# Controller_Board_Interface.net
KiCad netlist of a schematic drawn in Altium Designer
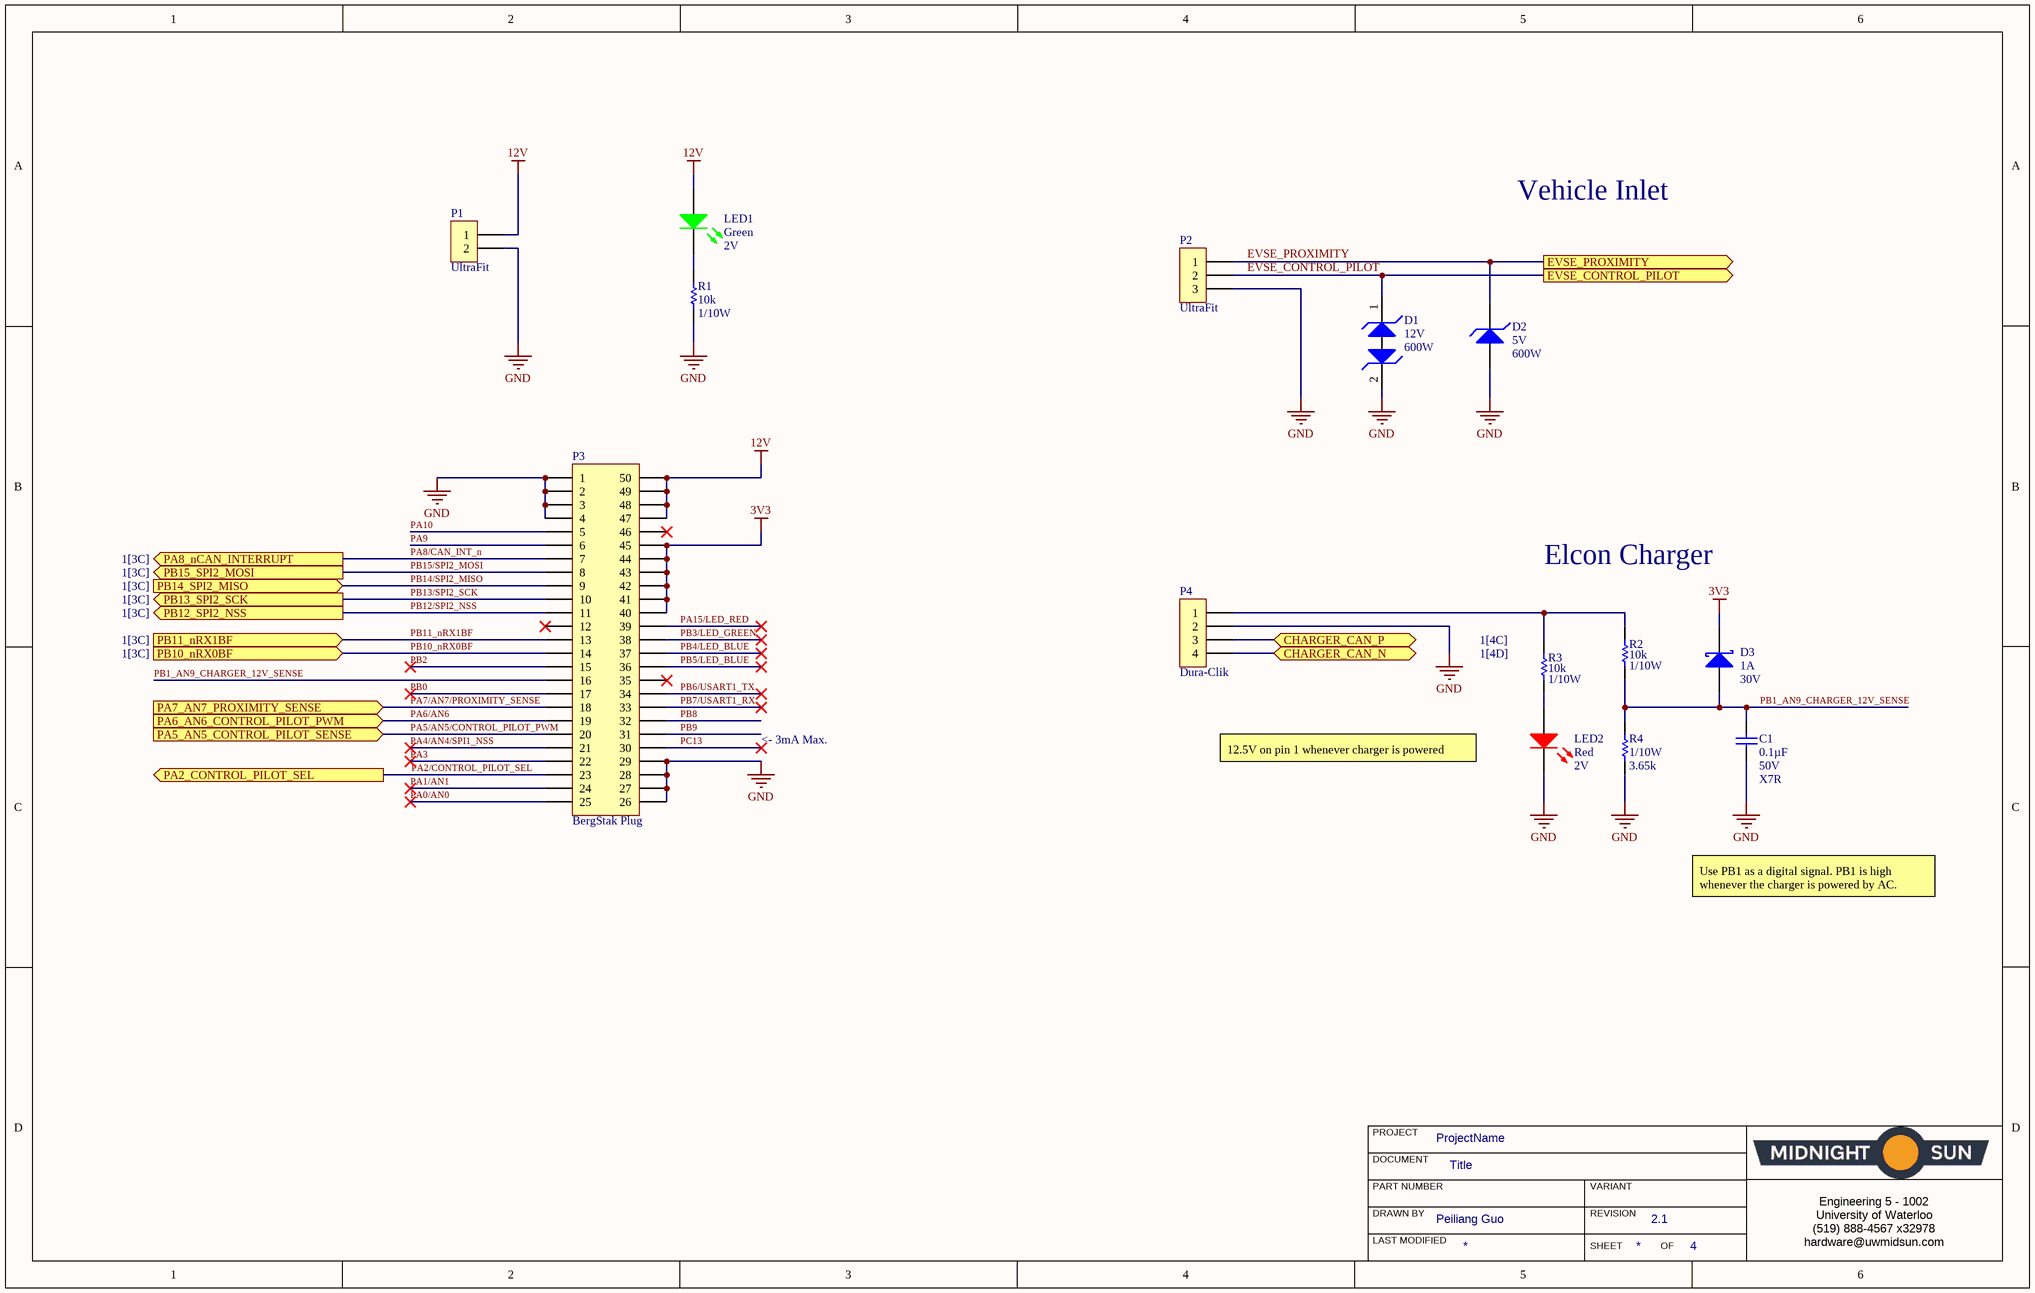
[diagram p0: Controller_Board_Interface.SchDoc]

(export (version "E")
  (design (tool "Eeschema 10.0.6"))
  (components
    (comp (ref "C1")
      (value "CAP CER 0.1UF 50V 10% X7R 0603")
      (footprint "CAP, 0603")
      (description "0.10µF ±10% 50V Ceramic Capacitor X7R 0603 (1608 Metric)")
      (fields
        (field (name "TOLERANCE") "±10%")
        (field (name "CAPACITANCE") "0.1µF")
        (field (name "VOLTAGE") "50V")
        (field (name "TEMPERATURE COEFFICIENT") "X7R")
      )
      (libsource (lib "altium-import") (part "root_0_CAP CER 0.1UF 50V 10% X7R 0603_"))
    )
    (comp (ref "D1")
      (value "DIODE TVS 12VWM 19.6VC DO-214AA (SMB)")
      (footprint "DO-214AA Diode")
      (description "TVS DIODE 12V 19.6V DO214AA")
      (fields
        (field (name "MANUFACTURER") "Vishay Semiconductor Diodes Division")
        (field (name "MANUFACTURER PART NUMBER") "SMBJ12CD-M3/H")
        (field (name "VOLTAGE - REVERSE STANDOFF (TYP)") "12V")
        (field (name "POWER - PEAK PULSE") "600W")
      )
      (libsource (lib "Schematic Diagrams") (part "DIODE TVS 12VWM 19.6VC DO-214AA (SMB)"))
    )
    (comp (ref "D2")
      (value "DIODE TVS 5VWM 9.1VC DO-214AA (SMB)")
      (footprint "DO-214AA Diode")
      (description "TVS DIODE 5V 9.1V DO214AA")
      (fields
        (field (name "MANUFACTURER") "Vishay Semiconductor Diodes Division")
        (field (name "MANUFACTURER PART NUMBER") "SMBJ5.0D-M3/H")
        (field (name "VOLTAGE - REVERSE STANDOFF (TYP)") "5V")
        (field (name "POWER - PEAK PULSE") "600W")
      )
      (libsource (lib "Schematic Diagrams") (part "DIODE TVS 5VWM 9.1VC DO-214AA (SMB)"))
    )
    (comp (ref "D3")
      (value "DIODE SCHOTTKY 30V 1A POWERDI123")
      (footprint "DIODE SCHOTTKY 30V 1A POWERDI123")
      (description "Diode Schottky 30V 1A Surface Mount PowerDI™ 123")
      (fields
        (field (name "MANUFACTURER") "Diodes Incorporated")
        (field (name "MANUFACTURER PART NUMBER") "DFLS130L-7")
        (field (name "CURRENT - AVERAGE RECTIFIED (IO)") "1A")
        (field (name "VOLTAGE - DC REVERSE (VR) (MAX)") "30V")
      )
      (libsource (lib "Schematic Diagrams") (part "DIODE SCHOTTKY 30V 1A POWERDI123"))
    )
    (comp (ref "LED1")
      (value "LED GREEN CLEAR 2V 0603")
      (footprint "LED_0603")
      (description "Green 572nm LED Indication - Discrete 2V 0603 (1608 Metric)")
      (fields
        (field (name "MANUFACTURER") "Wurth Electronics Inc.")
        (field (name "MANUFACTURER PART NUMBER") "150060VS75000")
        (field (name "COLOR") "Green")
        (field (name "VOLTAGE - FORWARD (VF) (TYP)") "2V")
      )
      (libsource (lib "Schematic Diagrams") (part "LED GREEN CLEAR 2V 0603"))
    )
    (comp (ref "LED2")
      (value "LED RED CLEAR 2V 0603")
      (footprint "LED_0603")
      (description "Red 631nm LED Indication - Discrete 2V 0603 (1608 Metric)")
      (fields
        (field (name "MANUFACTURER") "Wurth Electronics Inc.")
        (field (name "MANUFACTURER PART NUMBER") "150060RS75000")
        (field (name "COLOR") "Red")
        (field (name "VOLTAGE - FORWARD (VF) (TYP)") "2V")
      )
      (libsource (lib "altium-import") (part "root_3_LED RED CLEAR 2V 0603_"))
    )
    (comp (ref "P1")
      (value "CONN 2POS ULTRA-FIT 0.138\"")
      (footprint "CONN, 2POS ULTRA-FIT")
      (description "2 Positions Header, Shrouded Connector 0.138\" (3.50mm) Through Hole Gold")
      (fields (field (name "VOLTAGE") "400V") (field (name "SERIES") "UltraFit"))
      (libsource (lib "Schematic Diagrams") (part "CONN 2POS ULTRA-FIT 0.138{dblquote}"))
    )
    (comp (ref "P2")
      (value "CONN 3POS ULTRA-FIT 0.138\"")
      (footprint "CONN, 3POS ULTRA-FIT")
      (description "3 Positions Header Connector 0.138\" (3.50mm) Through Hole Tin")
      (fields (field (name "VOLTAGE") "400V") (field (name "SERIES") "UltraFit"))
      (libsource (lib "altium-import") (part "root_0_CONN 3POS ULTRA-FIT 0.138{dblquote}_"))
    )
    (comp (ref "P3")
      (value "CONN 50POS Bergstak Plug 0.02\"")
      (footprint "CONN, Bergstak 50 Pos Plug")
      (description "50 Position Connector Plug, Outer Shroud Contacts Surface Mount Gold")
      (fields (field (name "SERIES") "BergStak Plug"))
      (libsource (lib "Schematic Diagrams") (part "CONN 50POS Bergstak Plug 0.02{dblquote}"))
    )
    (comp (ref "P4")
      (value "Dura-Clik")
      (footprint "CONN, 4POS DURA-CLIK VERT")
      (description "4 Positions Header Connector 0.079\" (2.00mm) Surface Mount Tin")
      (fields
        (field (name "MANUFACTURER") "Molex, LLC")
        (field (name "MANUFACTURER PART NUMBER") "5600200420")
      )
      (libsource (lib "Schematic Diagrams") (part "CONN 4POS DURA-CLIK 0.079{dblquote}"))
    )
    (comp (ref "R1")
      (value "RES 10K OHM 1% 1/10W 0603")
      (footprint "RES, 0603")
      (description "RES SMD 10K OHM 1% 1/10W 0603")
      (fields
        (field (name "TOLERANCE") "±1%")
        (field (name "RESISTANCE") "10k")
        (field (name "POWER") "1/10W")
      )
      (libsource (lib "Schematic Diagrams") (part "RES 10K OHM 1% 1/10W 0603"))
    )
    (comp (ref "R2")
      (value "RES 10K OHM 1% 1/10W 0603")
      (footprint "RES, 0603")
      (description "RES SMD 10K OHM 1% 1/10W 0603")
      (fields
        (field (name "TOLERANCE") "±1%")
        (field (name "RESISTANCE") "10k")
        (field (name "POWER") "1/10W")
      )
      (libsource (lib "Schematic Diagrams") (part "RES 10K OHM 1% 1/10W 0603"))
    )
    (comp (ref "R3")
      (value "RES 10K OHM 1% 1/10W 0603")
      (footprint "RES, 0603")
      (description "RES SMD 10K OHM 1% 1/10W 0603")
      (fields
        (field (name "TOLERANCE") "±1%")
        (field (name "RESISTANCE") "10k")
        (field (name "POWER") "1/10W")
      )
      (libsource (lib "Schematic Diagrams") (part "RES 10K OHM 1% 1/10W 0603"))
    )
    (comp (ref "R4")
      (value "RES 3.65K OHM 0.1% 1/10W 0603")
      (footprint "RES, 0603")
      (description "3.65 kOhms ±0.1% 0.1W, 1/10W Chip Resistor 0603 (1608 Metric) Automotive AEC-Q200 Thin Film")
      (fields
        (field (name "MANUFACTURER") "Panasonic")
        (field (name "MANUFACTURER PART NUMBER") "ERA3AEB3651V")
        (field (name "POWER RATING") "1/10W")
        (field (name "RESISTANCE") "3.65k")
      )
      (libsource (lib "Schematic Diagrams") (part "RES 3.65K OHM 0.1% 1/10W 0603"))
    )
  )
  (nets
    (net (code "1") (name "/CHARGER_CAN_N") (class "Default")
      (node (ref "P4") (pin "4") (pinfunction "4_4") (pintype "passive"))
    )
    (net (code "2") (name "/CHARGER_CAN_P") (class "Default")
      (node (ref "P4") (pin "3") (pinfunction "3_3") (pintype "passive"))
    )
    (net (code "3") (name "/EVSE_CONTROL_PILOT") (class "Default")
      (node (ref "D1") (pin "1") (pinfunction "Cathode1_1") (pintype "passive"))
      (node (ref "P2") (pin "2") (pinfunction "2_2") (pintype "passive"))
    )
    (net (code "4") (name "/EVSE_PROXIMITY") (class "Default")
      (node (ref "D2") (pin "2") (pinfunction "2_2") (pintype "passive"))
      (node (ref "P2") (pin "1") (pinfunction "1_1") (pintype "passive"))
    )
    (net (code "5") (name "/PA0{slash}AN0") (class "Default")
      (node (ref "P3") (pin "25") (pinfunction "25_25") (pintype "passive+no_connect"))
    )
    (net (code "6") (name "/PA1{slash}AN1") (class "Default")
      (node (ref "P3") (pin "24") (pinfunction "24_24") (pintype "passive+no_connect"))
    )
    (net (code "7") (name "/PA2{slash}CONTROL_PILOT_SEL") (class "Default")
      (node (ref "P3") (pin "23") (pinfunction "23_23") (pintype "passive"))
    )
    (net (code "8") (name "/PA3") (class "Default")
      (node (ref "P3") (pin "22") (pinfunction "22_22") (pintype "passive+no_connect"))
    )
    (net (code "9") (name "/PA4{slash}AN4{slash}SPI1_NSS") (class "Default")
      (node (ref "P3") (pin "21") (pinfunction "21_21") (pintype "passive+no_connect"))
    )
    (net (code "10") (name "/PA5{slash}AN5{slash}CONTROL_PILOT_PWM") (class "Default")
      (node (ref "P3") (pin "20") (pinfunction "20_20") (pintype "passive"))
    )
    (net (code "11") (name "/PA6{slash}AN6") (class "Default")
      (node (ref "P3") (pin "19") (pinfunction "19_19") (pintype "passive"))
    )
    (net (code "12") (name "/PA7{slash}AN7{slash}PROXIMITY_SENSE") (class "Default")
      (node (ref "P3") (pin "18") (pinfunction "18_18") (pintype "passive"))
    )
    (net (code "13") (name "/PA8{slash}CAN_INT_n") (class "Default")
      (node (ref "P3") (pin "7") (pinfunction "7_7") (pintype "passive"))
    )
    (net (code "14") (name "/PA9") (class "Default")
      (node (ref "P3") (pin "6") (pinfunction "6_6") (pintype "passive"))
    )
    (net (code "15") (name "/PA10") (class "Default")
      (node (ref "P3") (pin "5") (pinfunction "5_5") (pintype "passive"))
    )
    (net (code "16") (name "/PA15{slash}LED_RED") (class "Default")
      (node (ref "P3") (pin "39") (pinfunction "39_39") (pintype "passive+no_connect"))
    )
    (net (code "17") (name "/PB0") (class "Default")
      (node (ref "P3") (pin "17") (pinfunction "17_17") (pintype "passive+no_connect"))
    )
    (net (code "18") (name "/PB1_AN9_CHARGER_12V_SENSE") (class "Default")
      (node (ref "C1") (pin "1") (pinfunction "1_1") (pintype "passive"))
      (node (ref "D3") (pin "1") (pinfunction "A_1") (pintype "passive"))
      (node (ref "P3") (pin "16") (pinfunction "16_16") (pintype "passive"))
      (node (ref "R2") (pin "2") (pinfunction "2_2") (pintype "passive"))
      (node (ref "R4") (pin "1") (pinfunction "1_1") (pintype "passive"))
    )
    (net (code "19") (name "/PB2") (class "Default")
      (node (ref "P3") (pin "15") (pinfunction "15_15") (pintype "passive+no_connect"))
    )
    (net (code "20") (name "/PB3{slash}LED_GREEN") (class "Default")
      (node (ref "P3") (pin "38") (pinfunction "38_38") (pintype "passive+no_connect"))
    )
    (net (code "21") (name "/PB4{slash}LED_BLUE") (class "Default")
      (node (ref "P3") (pin "37") (pinfunction "37_37") (pintype "passive+no_connect"))
    )
    (net (code "22") (name "/PB5{slash}LED_BLUE") (class "Default")
      (node (ref "P3") (pin "36") (pinfunction "36_36") (pintype "passive+no_connect"))
    )
    (net (code "23") (name "/PB6{slash}USART1_TX") (class "Default")
      (node (ref "P3") (pin "34") (pinfunction "34_34") (pintype "passive+no_connect"))
    )
    (net (code "24") (name "/PB7{slash}USART1_RX") (class "Default")
      (node (ref "P3") (pin "33") (pinfunction "33_33") (pintype "passive+no_connect"))
    )
    (net (code "25") (name "/PB8") (class "Default")
      (node (ref "P3") (pin "32") (pinfunction "32_32") (pintype "passive"))
    )
    (net (code "26") (name "/PB9") (class "Default")
      (node (ref "P3") (pin "31") (pinfunction "31_31") (pintype "passive"))
    )
    (net (code "27") (name "/PB10_nRX0BF") (class "Default")
      (node (ref "P3") (pin "14") (pinfunction "14_14") (pintype "passive"))
    )
    (net (code "28") (name "/PB11_nRX1BF") (class "Default")
      (node (ref "P3") (pin "13") (pinfunction "13_13") (pintype "passive"))
    )
    (net (code "29") (name "/PB12{slash}SPI2_NSS") (class "Default")
      (node (ref "P3") (pin "11") (pinfunction "11_11") (pintype "passive"))
    )
    (net (code "30") (name "/PB13{slash}SPI2_SCK") (class "Default")
      (node (ref "P3") (pin "10") (pinfunction "10_10") (pintype "passive"))
    )
    (net (code "31") (name "/PB14{slash}SPI2_MISO") (class "Default")
      (node (ref "P3") (pin "9") (pinfunction "9_9") (pintype "passive"))
    )
    (net (code "32") (name "/PB15{slash}SPI2_MOSI") (class "Default")
      (node (ref "P3") (pin "8") (pinfunction "8_8") (pintype "passive"))
    )
    (net (code "33") (name "/PC13") (class "Default")
      (node (ref "P3") (pin "30") (pinfunction "30_30") (pintype "passive+no_connect"))
    )
    (net (code "34") (name "3V3") (class "Default")
      (node (ref "D3") (pin "2") (pinfunction "K_2") (pintype "passive"))
      (node (ref "P3") (pin "40") (pinfunction "40_40") (pintype "passive"))
      (node (ref "P3") (pin "41") (pinfunction "41_41") (pintype "passive"))
      (node (ref "P3") (pin "42") (pinfunction "42_42") (pintype "passive"))
      (node (ref "P3") (pin "43") (pinfunction "43_43") (pintype "passive"))
      (node (ref "P3") (pin "44") (pinfunction "44_44") (pintype "passive"))
      (node (ref "P3") (pin "45") (pinfunction "45_45") (pintype "passive"))
    )
    (net (code "35") (name "12V") (class "Default")
      (node (ref "LED1") (pin "1") (pinfunction "A_1") (pintype "passive"))
      (node (ref "P1") (pin "1") (pinfunction "1_1") (pintype "passive"))
      (node (ref "P3") (pin "47") (pinfunction "47_47") (pintype "passive"))
      (node (ref "P3") (pin "48") (pinfunction "48_48") (pintype "passive"))
      (node (ref "P3") (pin "49") (pinfunction "49_49") (pintype "passive"))
      (node (ref "P3") (pin "50") (pinfunction "50_50") (pintype "passive"))
    )
    (net (code "36") (name "GND") (class "Default")
      (node (ref "C1") (pin "2") (pinfunction "2_2") (pintype "passive"))
      (node (ref "D1") (pin "2") (pinfunction "Cathode2_2") (pintype "passive"))
      (node (ref "D2") (pin "1") (pinfunction "1_1") (pintype "passive"))
      (node (ref "LED2") (pin "2") (pinfunction "K_2") (pintype "passive"))
      (node (ref "P1") (pin "2") (pinfunction "2_2") (pintype "passive"))
      (node (ref "P2") (pin "3") (pinfunction "3_3") (pintype "passive"))
      (node (ref "P3") (pin "1") (pinfunction "1_1") (pintype "passive"))
      (node (ref "P3") (pin "2") (pinfunction "2_2") (pintype "passive"))
      (node (ref "P3") (pin "26") (pinfunction "26_26") (pintype "passive"))
      (node (ref "P3") (pin "27") (pinfunction "27_27") (pintype "passive"))
      (node (ref "P3") (pin "28") (pinfunction "28_28") (pintype "passive"))
      (node (ref "P3") (pin "29") (pinfunction "29_29") (pintype "passive"))
      (node (ref "P3") (pin "3") (pinfunction "3_3") (pintype "passive"))
      (node (ref "P3") (pin "4") (pinfunction "4_4") (pintype "passive"))
      (node (ref "P4") (pin "2") (pinfunction "2_2") (pintype "passive"))
      (node (ref "R1") (pin "2") (pinfunction "2_2") (pintype "passive"))
      (node (ref "R4") (pin "2") (pinfunction "2_2") (pintype "passive"))
    )
    (net (code "37") (name "Net-(LED1-K)") (class "Default")
      (node (ref "LED1") (pin "2") (pinfunction "K_2") (pintype "passive"))
      (node (ref "R1") (pin "1") (pinfunction "1_1") (pintype "passive"))
    )
    (net (code "38") (name "Net-(LED2-A)") (class "Default")
      (node (ref "LED2") (pin "1") (pinfunction "A_1") (pintype "passive"))
      (node (ref "R3") (pin "2") (pinfunction "2_2") (pintype "passive"))
    )
    (net (code "39") (name "Net-(P4-Pad1)") (class "Default")
      (node (ref "P4") (pin "1") (pinfunction "1_1") (pintype "passive"))
      (node (ref "R2") (pin "1") (pinfunction "1_1") (pintype "passive"))
      (node (ref "R3") (pin "1") (pinfunction "1_1") (pintype "passive"))
    )
    (net (code "40") (name "unconnected-(P3-Pad12)") (class "Default")
      (node (ref "P3") (pin "12") (pinfunction "12_12") (pintype "passive+no_connect"))
    )
    (net (code "41") (name "unconnected-(P3-Pad35)") (class "Default")
      (node (ref "P3") (pin "35") (pinfunction "35_35") (pintype "passive+no_connect"))
    )
    (net (code "42") (name "unconnected-(P3-Pad46)") (class "Default")
      (node (ref "P3") (pin "46") (pinfunction "46_46") (pintype "passive+no_connect"))
    )
  )
)
